# AnalogConnector.net
KiCad netlist of a schematic drawn in Altium Designer
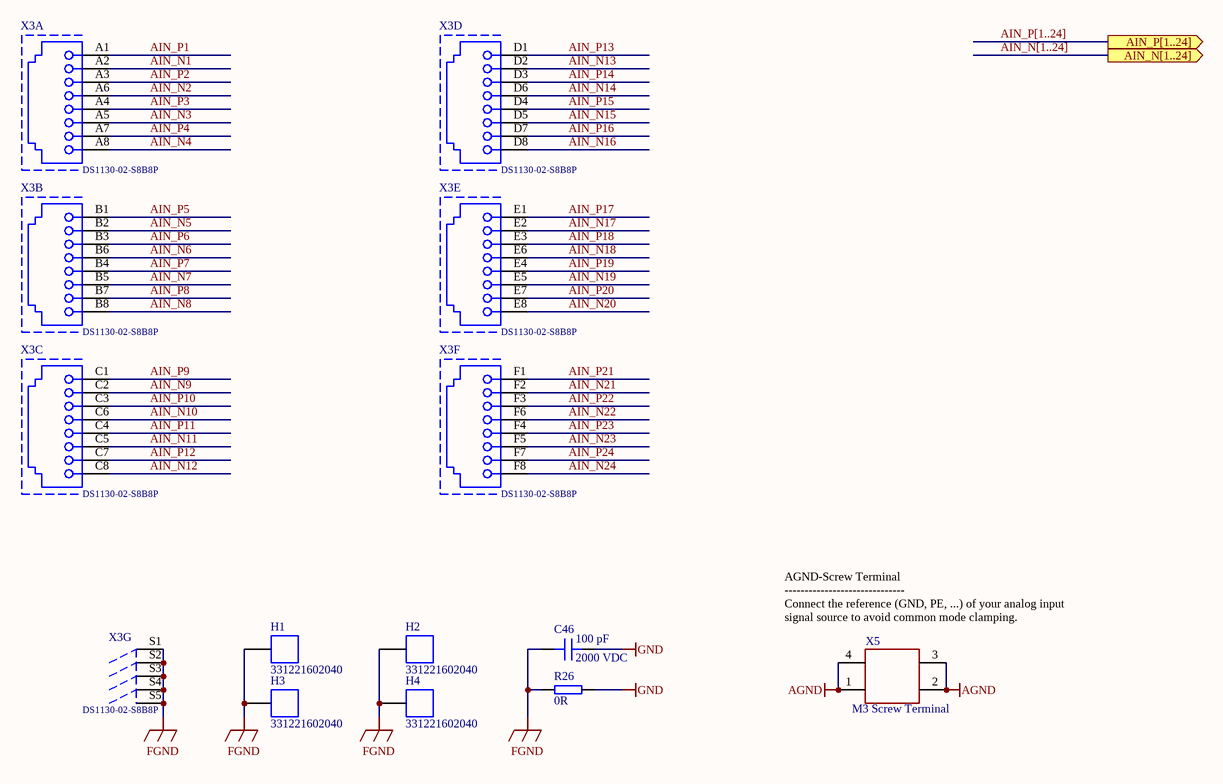
[diagram p0: AnalogConnector.SchDoc]

(export (version "E")
  (design (tool "Eeschema 10.0.6"))
  (components
    (comp (ref "C46")
      (value "100 pF")
      (footprint "C_1206")
      (description "2kV 100pF NP0 ±5% 1206 Multilayer Ceramic Capacitors MLCC - SMD/SMT ROHS")
      (fields
        (field (name "MANUFACTURER PART NUMBER") "CC1206JKNPODBN101")
        (field (name "MANUFACTURER") "YAGEO")
        (field (name "VOLTAGE RATING") "2000 VDC")
        (field (name "CREATED FROM") "AGeiger")
      )
      (libsource (lib "user") (part "Capacitor"))
    )
    (comp (ref "H1")
      (value "331221602040")
      (footprint "331221602040")
      (description "Contact Finger between PCB's earth and housing")
      (fields (field (name "MANUFACTURER") "Wuerth Elektronik") (field (name "CREATED FROM") "AGeiger"))
      (libsource (lib "user") (part "331221602040"))
    )
    (comp (ref "H2")
      (value "331221602040")
      (footprint "331221602040")
      (description "Contact Finger between PCB's earth and housing")
      (fields (field (name "MANUFACTURER") "Wuerth Elektronik") (field (name "CREATED FROM") "AGeiger"))
      (libsource (lib "user") (part "331221602040"))
    )
    (comp (ref "H3")
      (value "331221602040")
      (footprint "331221602040")
      (description "Contact Finger between PCB's earth and housing")
      (fields (field (name "MANUFACTURER") "Wuerth Elektronik") (field (name "CREATED FROM") "AGeiger"))
      (libsource (lib "user") (part "331221602040"))
    )
    (comp (ref "H4")
      (value "331221602040")
      (footprint "331221602040")
      (description "Contact Finger between PCB's earth and housing")
      (fields (field (name "MANUFACTURER") "Wuerth Elektronik") (field (name "CREATED FROM") "AGeiger"))
      (libsource (lib "user") (part "331221602040"))
    )
    (comp (ref "R26")
      (value "0R")
      (footprint "R_1206_TE")
      (description "Generic resistor")
      (fields
        (field (name "MANUFACTURER PART NUMBER") "UZgen_R_1206_0R")
        (field (name "MANUFACTURER") "UZgen")
        (field (name "CREATED FROM") "UZgenTool")
      )
      (libsource (lib "user") (part "RES"))
    )
    (comp (ref "X3")
      (value "DS1130-02-S8B8P")
      (footprint "DS1130-02-S8B8P")
      (description "RJ45 RJReceptacle 6 No Plugin Ethernet Connectors/Modular Connectors (RJ45 RJ11) ROHS")
      (fields
        (field (name "MANUFACTURER") "CONNFLY Elec")
        (field (name "LCSC PART NUMBER") "C86584")
        (field (name "CREATED FROM") "AGeiger")
      )
      (libsource (lib "user") (part "DS1130-02-S8B8P"))
    )
    (comp (ref "X5")
      (value "M3 Screw Terminal")
      (footprint "KEYSTONE_7698")
      (description "Tin 15A Brass 4 Through Hole M3x0.5 Screw Connectors ROHS")
      (fields
        (field (name "MANUFACTURER PART NUMBER") "Keystone")
        (field (name "LCSC PART NUMBER") "C6708741")
        (field (name "CREATED FROM") "AGeiger")
      )
      (libsource (lib "user") (part "7698"))
    )
  )
  (nets
    (net (code "1") (name "/AIN_N1") (class "Default")
      (node (ref "X3") (pin "A2") (pinfunction "A2_A2") (pintype "passive"))
    )
    (net (code "2") (name "/AIN_N2") (class "Default")
      (node (ref "X3") (pin "A6") (pinfunction "A6_A6") (pintype "passive"))
    )
    (net (code "3") (name "/AIN_N3") (class "Default")
      (node (ref "X3") (pin "A5") (pinfunction "A5_A5") (pintype "passive"))
    )
    (net (code "4") (name "/AIN_N4") (class "Default")
      (node (ref "X3") (pin "A8") (pinfunction "A8_A8") (pintype "passive"))
    )
    (net (code "5") (name "/AIN_N5") (class "Default")
      (node (ref "X3") (pin "B2") (pinfunction "B2_B2") (pintype "passive"))
    )
    (net (code "6") (name "/AIN_N6") (class "Default")
      (node (ref "X3") (pin "B6") (pinfunction "B6_B6") (pintype "passive"))
    )
    (net (code "7") (name "/AIN_N7") (class "Default")
      (node (ref "X3") (pin "B5") (pinfunction "B5_B5") (pintype "passive"))
    )
    (net (code "8") (name "/AIN_N8") (class "Default")
      (node (ref "X3") (pin "B8") (pinfunction "B8_B8") (pintype "passive"))
    )
    (net (code "9") (name "/AIN_N9") (class "Default")
      (node (ref "X3") (pin "C2") (pinfunction "C2_C2") (pintype "passive"))
    )
    (net (code "10") (name "/AIN_N10") (class "Default")
      (node (ref "X3") (pin "C6") (pinfunction "C6_C6") (pintype "passive"))
    )
    (net (code "11") (name "/AIN_N11") (class "Default")
      (node (ref "X3") (pin "C5") (pinfunction "C5_C5") (pintype "passive"))
    )
    (net (code "12") (name "/AIN_N12") (class "Default")
      (node (ref "X3") (pin "C8") (pinfunction "C8_C8") (pintype "passive"))
    )
    (net (code "13") (name "/AIN_N13") (class "Default")
      (node (ref "X3") (pin "D2") (pinfunction "D2_D2") (pintype "passive"))
    )
    (net (code "14") (name "/AIN_N14") (class "Default")
      (node (ref "X3") (pin "D6") (pinfunction "D6_D6") (pintype "passive"))
    )
    (net (code "15") (name "/AIN_N15") (class "Default")
      (node (ref "X3") (pin "D5") (pinfunction "D5_D5") (pintype "passive"))
    )
    (net (code "16") (name "/AIN_N16") (class "Default")
      (node (ref "X3") (pin "D8") (pinfunction "D8_D8") (pintype "passive"))
    )
    (net (code "17") (name "/AIN_N17") (class "Default")
      (node (ref "X3") (pin "E2") (pinfunction "E2_E2") (pintype "passive"))
    )
    (net (code "18") (name "/AIN_N18") (class "Default")
      (node (ref "X3") (pin "E6") (pinfunction "E6_E6") (pintype "passive"))
    )
    (net (code "19") (name "/AIN_N19") (class "Default")
      (node (ref "X3") (pin "E5") (pinfunction "E5_E5") (pintype "passive"))
    )
    (net (code "20") (name "/AIN_N20") (class "Default")
      (node (ref "X3") (pin "E8") (pinfunction "E8_E8") (pintype "passive"))
    )
    (net (code "21") (name "/AIN_N21") (class "Default")
      (node (ref "X3") (pin "F2") (pinfunction "F2_F2") (pintype "passive"))
    )
    (net (code "22") (name "/AIN_N22") (class "Default")
      (node (ref "X3") (pin "F6") (pinfunction "F6_F6") (pintype "passive"))
    )
    (net (code "23") (name "/AIN_N23") (class "Default")
      (node (ref "X3") (pin "F5") (pinfunction "F5_F5") (pintype "passive"))
    )
    (net (code "24") (name "/AIN_N24") (class "Default")
      (node (ref "X3") (pin "F8") (pinfunction "F8_F8") (pintype "passive"))
    )
    (net (code "26") (name "/AIN_P1") (class "Default")
      (node (ref "X3") (pin "A1") (pinfunction "A1_A1") (pintype "passive"))
    )
    (net (code "27") (name "/AIN_P2") (class "Default")
      (node (ref "X3") (pin "A3") (pinfunction "A3_A3") (pintype "passive"))
    )
    (net (code "28") (name "/AIN_P3") (class "Default")
      (node (ref "X3") (pin "A4") (pinfunction "A4_A4") (pintype "passive"))
    )
    (net (code "29") (name "/AIN_P4") (class "Default")
      (node (ref "X3") (pin "A7") (pinfunction "A7_A7") (pintype "passive"))
    )
    (net (code "30") (name "/AIN_P5") (class "Default")
      (node (ref "X3") (pin "B1") (pinfunction "B1_B1") (pintype "passive"))
    )
    (net (code "31") (name "/AIN_P6") (class "Default")
      (node (ref "X3") (pin "B3") (pinfunction "B3_B3") (pintype "passive"))
    )
    (net (code "32") (name "/AIN_P7") (class "Default")
      (node (ref "X3") (pin "B4") (pinfunction "B4_B4") (pintype "passive"))
    )
    (net (code "33") (name "/AIN_P8") (class "Default")
      (node (ref "X3") (pin "B7") (pinfunction "B7_B7") (pintype "passive"))
    )
    (net (code "34") (name "/AIN_P9") (class "Default")
      (node (ref "X3") (pin "C1") (pinfunction "C1_C1") (pintype "passive"))
    )
    (net (code "35") (name "/AIN_P10") (class "Default")
      (node (ref "X3") (pin "C3") (pinfunction "C3_C3") (pintype "passive"))
    )
    (net (code "36") (name "/AIN_P11") (class "Default")
      (node (ref "X3") (pin "C4") (pinfunction "C4_C4") (pintype "passive"))
    )
    (net (code "37") (name "/AIN_P12") (class "Default")
      (node (ref "X3") (pin "C7") (pinfunction "C7_C7") (pintype "passive"))
    )
    (net (code "38") (name "/AIN_P13") (class "Default")
      (node (ref "X3") (pin "D1") (pinfunction "D1_D1") (pintype "passive"))
    )
    (net (code "39") (name "/AIN_P14") (class "Default")
      (node (ref "X3") (pin "D3") (pinfunction "D3_D3") (pintype "passive"))
    )
    (net (code "40") (name "/AIN_P15") (class "Default")
      (node (ref "X3") (pin "D4") (pinfunction "D4_D4") (pintype "passive"))
    )
    (net (code "41") (name "/AIN_P16") (class "Default")
      (node (ref "X3") (pin "D7") (pinfunction "D7_D7") (pintype "passive"))
    )
    (net (code "42") (name "/AIN_P17") (class "Default")
      (node (ref "X3") (pin "E1") (pinfunction "E1_E1") (pintype "passive"))
    )
    (net (code "43") (name "/AIN_P18") (class "Default")
      (node (ref "X3") (pin "E3") (pinfunction "E3_E3") (pintype "passive"))
    )
    (net (code "44") (name "/AIN_P19") (class "Default")
      (node (ref "X3") (pin "E4") (pinfunction "E4_E4") (pintype "passive"))
    )
    (net (code "45") (name "/AIN_P20") (class "Default")
      (node (ref "X3") (pin "E7") (pinfunction "E7_E7") (pintype "passive"))
    )
    (net (code "46") (name "/AIN_P21") (class "Default")
      (node (ref "X3") (pin "F1") (pinfunction "F1_F1") (pintype "passive"))
    )
    (net (code "47") (name "/AIN_P22") (class "Default")
      (node (ref "X3") (pin "F3") (pinfunction "F3_F3") (pintype "passive"))
    )
    (net (code "48") (name "/AIN_P23") (class "Default")
      (node (ref "X3") (pin "F4") (pinfunction "F4_F4") (pintype "passive"))
    )
    (net (code "49") (name "/AIN_P24") (class "Default")
      (node (ref "X3") (pin "F7") (pinfunction "F7_F7") (pintype "passive"))
    )
    (net (code "51") (name "AGND") (class "Default")
      (node (ref "X5") (pin "1") (pinfunction "1_1") (pintype "passive"))
      (node (ref "X5") (pin "2") (pinfunction "1_2") (pintype "passive"))
      (node (ref "X5") (pin "3") (pinfunction "1_3") (pintype "passive"))
      (node (ref "X5") (pin "4") (pinfunction "1_4") (pintype "passive"))
    )
    (net (code "52") (name "FGND") (class "Default")
      (node (ref "C46") (pin "1") (pinfunction "1_1") (pintype "passive"))
      (node (ref "H1") (pin "1") (pinfunction "1_1") (pintype "passive"))
      (node (ref "H2") (pin "1") (pinfunction "1_1") (pintype "passive"))
      (node (ref "H3") (pin "1") (pinfunction "1_1") (pintype "passive"))
      (node (ref "H4") (pin "1") (pinfunction "1_1") (pintype "passive"))
      (node (ref "R26") (pin "1") (pinfunction "1_1") (pintype "passive"))
      (node (ref "X3") (pin "S1") (pinfunction "S1_S1") (pintype "passive"))
      (node (ref "X3") (pin "S2") (pinfunction "S2_S2") (pintype "passive"))
      (node (ref "X3") (pin "S3") (pinfunction "S3_S3") (pintype "passive"))
      (node (ref "X3") (pin "S4") (pinfunction "S4_S4") (pintype "passive"))
      (node (ref "X3") (pin "S5") (pinfunction "S5_S5") (pintype "passive"))
    )
    (net (code "53") (name "GND") (class "Default")
      (node (ref "C46") (pin "2") (pinfunction "2_2") (pintype "passive"))
      (node (ref "R26") (pin "2") (pinfunction "2_2") (pintype "passive"))
    )
  )
)
